# Power_V3.net
KiCad netlist of a schematic drawn in Altium Designer
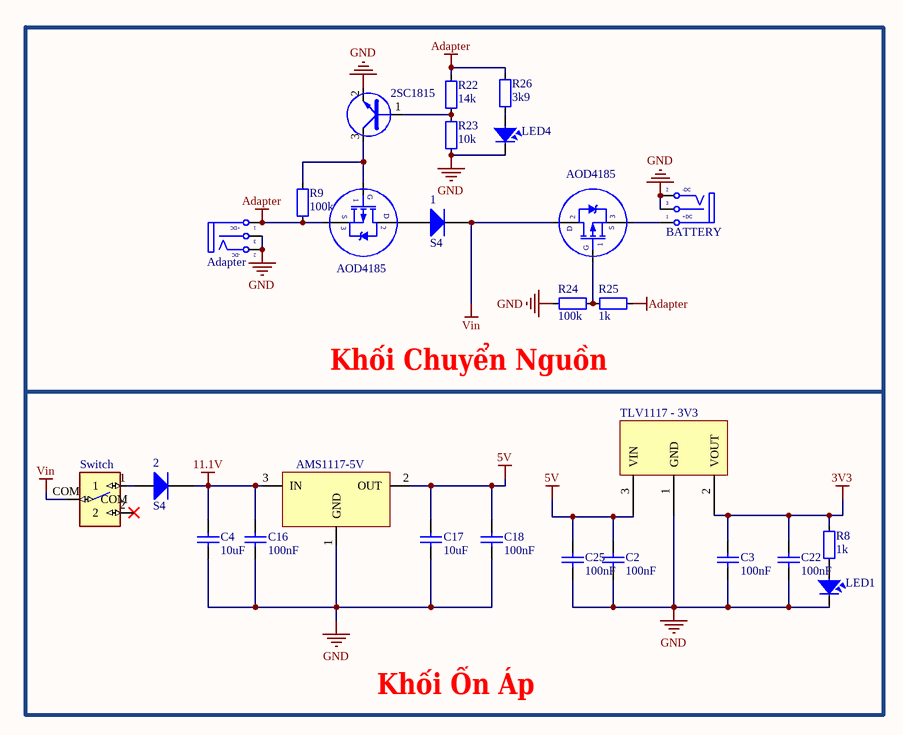
[diagram p0: Power_V3.SchDoc]

(export (version "E")
  (design (tool "Eeschema 10.0.6"))
  (components
    (comp (ref "1")
      (value "S4")
      (footprint "DIO-214AC(SMA)")
      (description "Dán")
      (libsource (lib "THU VIEN SCH") (part "Diode S4"))
    )
    (comp (ref "2")
      (value "S4")
      (footprint "DIO-214AC(SMA)")
      (description "Dán")
      (libsource (lib "THU VIEN SCH") (part "Diode S4"))
    )
    (comp (ref "C2")
      (value "100nF")
      (footprint "CAP_0805")
      (description "Capacitor")
      (fields (field (name "PUBLISHER") "Altium Limited"))
      (libsource (lib "My Library") (part "CapSMD"))
    )
    (comp (ref "C3")
      (value "100nF")
      (footprint "CAP_0805")
      (description "Capacitor")
      (fields (field (name "PUBLISHER") "Altium Limited"))
      (libsource (lib "My Library") (part "CapSMD"))
    )
    (comp (ref "C4")
      (value "10uF")
      (footprint "CAP_0805")
      (description "Capacitor")
      (fields (field (name "PUBLISHER") "Altium Limited"))
      (libsource (lib "My Library") (part "CapSMD"))
    )
    (comp (ref "C16")
      (value "100nF")
      (footprint "CAP_0805")
      (description "Capacitor")
      (fields (field (name "PUBLISHER") "Altium Limited"))
      (libsource (lib "My Library") (part "CapSMD"))
    )
    (comp (ref "C17")
      (value "10uF")
      (footprint "CAP_0805")
      (description "Capacitor")
      (fields (field (name "PUBLISHER") "Altium Limited"))
      (libsource (lib "My Library") (part "CapSMD"))
    )
    (comp (ref "C18")
      (value "100nF")
      (footprint "CAP_0805")
      (description "Capacitor")
      (fields (field (name "PUBLISHER") "Altium Limited"))
      (libsource (lib "My Library") (part "CapSMD"))
    )
    (comp (ref "C22")
      (value "100nF")
      (footprint "CAP_0805")
      (description "Capacitor")
      (fields (field (name "PUBLISHER") "Altium Limited"))
      (libsource (lib "My Library") (part "CapSMD"))
    )
    (comp (ref "C25")
      (value "100nF")
      (footprint "CAP_0805")
      (description "Capacitor")
      (fields (field (name "PUBLISHER") "Altium Limited"))
      (libsource (lib "My Library") (part "CapSMD"))
    )
    (comp (ref "IC2")
      (value "AOD4185")
      (footprint "TO-252")
      (description "Generic P Channel MOSFET")
      (libsource (lib "My Library") (part "MOSFET_P"))
    )
    (comp (ref "IC3")
      (value "AOD4185")
      (footprint "TO-252")
      (description "Generic P Channel MOSFET")
      (libsource (lib "My Library") (part "MOSFET_P"))
    )
    (comp (ref "JDC1")
      (value "Adapter")
      (footprint "DC-IN")
      (description "Jac DC input")
      (libsource (lib "My Library") (part "DCIN"))
    )
    (comp (ref "JDC2")
      (value "BATTERY")
      (footprint "DC-IN")
      (description "Jac DC input")
      (libsource (lib "My Library") (part "DCIN"))
    )
    (comp (ref "LED1")
      (value "LED")
      (footprint "LED-0805-Blue")
      (description "LED Single colour Green and Red")
      (libsource (lib "My Library") (part "LED"))
    )
    (comp (ref "LED4")
      (value "LED")
      (footprint "LED-0805-Blue")
      (description "LED Single colour Green and Red")
      (libsource (lib "My Library") (part "LED"))
    )
    (comp (ref "Power2")
      (value "AMS1117-5V")
      (footprint "SOT223")
      (description "800mA Low-Dropout Linear Regulator")
      (fields (field (name "CREATOR") "Nguyen Ba Bien"))
      (libsource (lib "LIBRARY1") (part "LM1117"))
    )
    (comp (ref "Q1")
      (value "2SC1815")
      (footprint "SOT23D")
      (description "NPN 600mW, ECB")
      (libsource (lib "My Library") (part "C1815"))
    )
    (comp (ref "R8")
      (value "1k")
      (footprint "RES-SMD-0805")
      (description "Resistor")
      (fields
        (field (name "MANUFACTURER") "Generic Components")
        (field (name "PUBLISHER") "Altium Hobart Technology Centre")
      )
      (libsource (lib "My Library") (part "Resistor - SMD"))
    )
    (comp (ref "R9")
      (value "100k")
      (footprint "RES-SMD-0805")
      (description "Resistor")
      (fields
        (field (name "MANUFACTURER") "Generic Components")
        (field (name "PUBLISHER") "Altium Hobart Technology Centre")
      )
      (libsource (lib "My Library") (part "Resistor - SMD"))
    )
    (comp (ref "R22")
      (value "14k")
      (footprint "RES-SMD-0805")
      (description "Resistor")
      (fields
        (field (name "MANUFACTURER") "Generic Components")
        (field (name "PUBLISHER") "Altium Hobart Technology Centre")
      )
      (libsource (lib "My Library") (part "Resistor - SMD"))
    )
    (comp (ref "R23")
      (value "10k")
      (footprint "RES-SMD-0805")
      (description "Resistor")
      (fields
        (field (name "MANUFACTURER") "Generic Components")
        (field (name "PUBLISHER") "Altium Hobart Technology Centre")
      )
      (libsource (lib "My Library") (part "Resistor - SMD"))
    )
    (comp (ref "R24")
      (value "100k")
      (footprint "RES-SMD-0805")
      (description "Resistor")
      (fields
        (field (name "MANUFACTURER") "Generic Components")
        (field (name "PUBLISHER") "Altium Hobart Technology Centre")
      )
      (libsource (lib "My Library") (part "Resistor - SMD"))
    )
    (comp (ref "R25")
      (value "1k")
      (footprint "RES-SMD-0805")
      (description "Resistor")
      (fields
        (field (name "MANUFACTURER") "Generic Components")
        (field (name "PUBLISHER") "Altium Hobart Technology Centre")
      )
      (libsource (lib "My Library") (part "Resistor - SMD"))
    )
    (comp (ref "R26")
      (value "3k9")
      (footprint "RES-SMD-0805")
      (description "Resistor")
      (fields
        (field (name "MANUFACTURER") "Generic Components")
        (field (name "PUBLISHER") "Altium Hobart Technology Centre")
      )
      (libsource (lib "My Library") (part "Resistor - SMD"))
    )
    (comp (ref "Switch")
      (value "SK12D07VG4")
      (footprint "SK12D07VG4")
      (description "Switch Slide ON ON SPDT Side Slide 0.3A 30VDC PC Pins Bracket Mount/Through Hole Bulk")
      (fields (field (name "MF") "C&K"))
      (libsource (lib "SK12D07VG4") (part "SK12D07VG4"))
    )
    (comp (ref "TLV1117 - 3V3")
      (value "LM1117- 5V")
      (footprint "SOT230P700X180-4N")
      (libsource (lib "hphonglib") (part "LM1117"))
    )
  )
  (nets
    (net (code "1") (name "3V3") (class "Default")
      (node (ref "C22") (pin "1") (pinfunction "1_1") (pintype "passive"))
      (node (ref "C3") (pin "1") (pinfunction "1_1") (pintype "passive"))
      (node (ref "R8") (pin "1") (pinfunction "1_1") (pintype "passive"))
      (node (ref "TLV1117 - 3V3") (pin "2") (pinfunction "VOUT_2") (pintype "passive"))
    )
    (net (code "2") (name "5V") (class "Default")
      (node (ref "C17") (pin "1") (pinfunction "1_1") (pintype "passive"))
      (node (ref "C18") (pin "1") (pinfunction "1_1") (pintype "passive"))
      (node (ref "C2") (pin "1") (pinfunction "1_1") (pintype "passive"))
      (node (ref "C25") (pin "1") (pinfunction "1_1") (pintype "passive"))
      (node (ref "Power2") (pin "2") (pinfunction "OUT_2") (pintype "passive"))
      (node (ref "TLV1117 - 3V3") (pin "3") (pinfunction "VIN_3") (pintype "passive"))
    )
    (net (code "3") (name "11.1V") (class "Default")
      (node (ref "2") (pin "2") (pinfunction "K_2") (pintype "passive"))
      (node (ref "C16") (pin "1") (pinfunction "1_1") (pintype "passive"))
      (node (ref "C4") (pin "1") (pinfunction "1_1") (pintype "passive"))
      (node (ref "Power2") (pin "3") (pinfunction "IN_3") (pintype "passive"))
    )
    (net (code "4") (name "Adapter") (class "Default")
      (node (ref "IC2") (pin "3") (pinfunction "S_3") (pintype "passive"))
      (node (ref "JDC1") (pin "1") (pinfunction "T_1") (pintype "passive"))
      (node (ref "R22") (pin "1") (pinfunction "1_1") (pintype "passive"))
      (node (ref "R25") (pin "1") (pinfunction "1_1") (pintype "passive"))
      (node (ref "R26") (pin "1") (pinfunction "1_1") (pintype "passive"))
      (node (ref "R9") (pin "1") (pinfunction "1_1") (pintype "passive"))
    )
    (net (code "5") (name "GND") (class "Default")
      (node (ref "C16") (pin "2") (pinfunction "2_2") (pintype "passive"))
      (node (ref "C17") (pin "2") (pinfunction "2_2") (pintype "passive"))
      (node (ref "C18") (pin "2") (pinfunction "2_2") (pintype "passive"))
      (node (ref "C2") (pin "2") (pinfunction "2_2") (pintype "passive"))
      (node (ref "C22") (pin "2") (pinfunction "2_2") (pintype "passive"))
      (node (ref "C25") (pin "2") (pinfunction "2_2") (pintype "passive"))
      (node (ref "C3") (pin "2") (pinfunction "2_2") (pintype "passive"))
      (node (ref "C4") (pin "2") (pinfunction "2_2") (pintype "passive"))
      (node (ref "JDC1") (pin "2") (pinfunction "TN_2") (pintype "passive"))
      (node (ref "JDC1") (pin "3") (pinfunction "S_3") (pintype "power_in"))
      (node (ref "JDC2") (pin "2") (pinfunction "TN_2") (pintype "passive"))
      (node (ref "JDC2") (pin "3") (pinfunction "S_3") (pintype "power_in"))
      (node (ref "LED1") (pin "2") (pinfunction "2_2") (pintype "passive"))
      (node (ref "LED4") (pin "2") (pinfunction "2_2") (pintype "passive"))
      (node (ref "Power2") (pin "1") (pinfunction "GND_1") (pintype "passive"))
      (node (ref "Q1") (pin "2") (pinfunction "E_2") (pintype "passive"))
      (node (ref "R23") (pin "2") (pinfunction "2_2") (pintype "passive"))
      (node (ref "R24") (pin "2") (pinfunction "2_2") (pintype "passive"))
      (node (ref "TLV1117 - 3V3") (pin "1") (pinfunction "GND_1") (pintype "passive"))
    )
    (net (code "6") (name "Net-(1-A)") (class "Default")
      (node (ref "1") (pin "1") (pinfunction "A_1") (pintype "passive"))
      (node (ref "IC2") (pin "2") (pinfunction "D_2") (pintype "passive"))
    )
    (net (code "7") (name "Net-(2-A)") (class "Default")
      (node (ref "2") (pin "1") (pinfunction "A_1") (pintype "passive"))
      (node (ref "Switch") (pin "1") (pinfunction "1_1") (pintype "bidirectional"))
    )
    (net (code "8") (name "Net-(IC2-G)") (class "Default")
      (node (ref "IC2") (pin "1") (pinfunction "G_1") (pintype "passive"))
      (node (ref "Q1") (pin "3") (pinfunction "C_3") (pintype "passive"))
      (node (ref "R9") (pin "2") (pinfunction "2_2") (pintype "passive"))
    )
    (net (code "9") (name "Net-(IC3-G)") (class "Default")
      (node (ref "IC3") (pin "1") (pinfunction "G_1") (pintype "passive"))
      (node (ref "R24") (pin "1") (pinfunction "1_1") (pintype "passive"))
      (node (ref "R25") (pin "2") (pinfunction "2_2") (pintype "passive"))
    )
    (net (code "10") (name "Net-(IC3-S)") (class "Default")
      (node (ref "IC3") (pin "3") (pinfunction "S_3") (pintype "passive"))
      (node (ref "JDC2") (pin "1") (pinfunction "T_1") (pintype "passive"))
    )
    (net (code "11") (name "Net-(LED1-Pad1)") (class "Default")
      (node (ref "LED1") (pin "1") (pinfunction "1_1") (pintype "passive"))
      (node (ref "R8") (pin "2") (pinfunction "2_2") (pintype "passive"))
    )
    (net (code "12") (name "Net-(LED4-Pad1)") (class "Default")
      (node (ref "LED4") (pin "1") (pinfunction "1_1") (pintype "passive"))
      (node (ref "R26") (pin "2") (pinfunction "2_2") (pintype "passive"))
    )
    (net (code "13") (name "Net-(Q1-B)") (class "Default")
      (node (ref "Q1") (pin "1") (pinfunction "B_1") (pintype "passive"))
      (node (ref "R22") (pin "2") (pinfunction "2_2") (pintype "passive"))
      (node (ref "R23") (pin "1") (pinfunction "1_1") (pintype "passive"))
    )
    (net (code "14") (name "Vin") (class "Default")
      (node (ref "1") (pin "2") (pinfunction "K_2") (pintype "passive"))
      (node (ref "IC3") (pin "2") (pinfunction "D_2") (pintype "passive"))
      (node (ref "Switch") (pin "COM") (pinfunction "COM_COM") (pintype "bidirectional"))
    )
    (net (code "15") (name "unconnected-(Switch-Pad2)") (class "Default")
      (node (ref "Switch") (pin "2") (pinfunction "2_2") (pintype "bidirectional+no_connect"))
    )
  )
)
